# schematic.net
KiCad netlist of a schematic drawn in Altium Designer
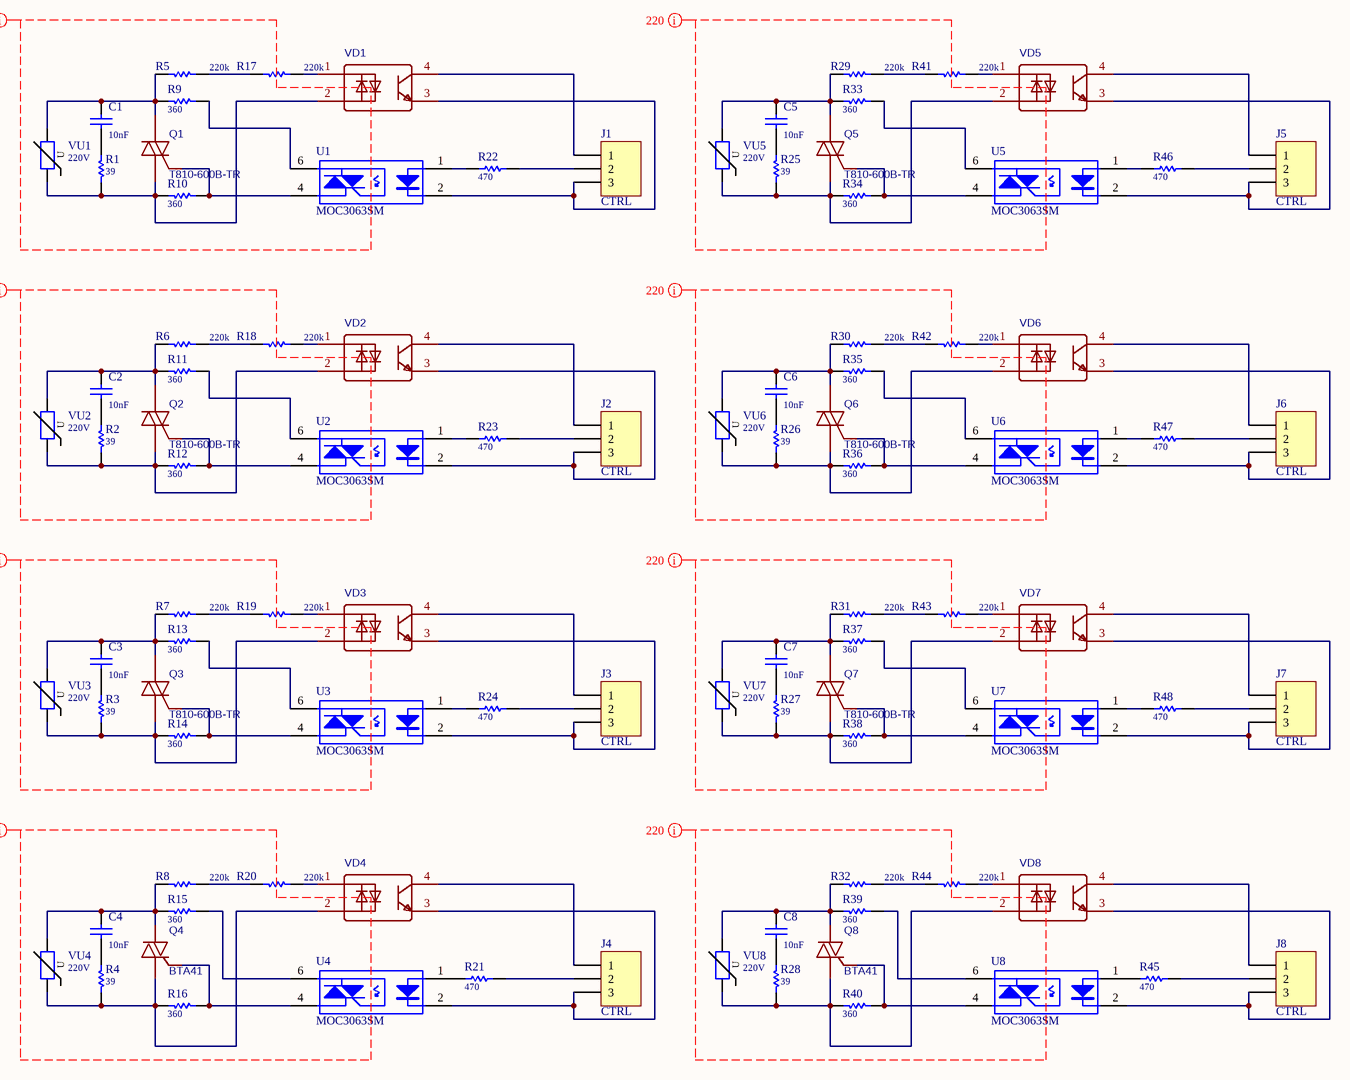
[diagram p0: schematic.SchDoc]

(export (version "E")
  (design (tool "Eeschema 10.0.6"))
  (components
    (comp (ref "C1")
      (value "10nF")
      (footprint "C1206")
      (description "10nF 1kV 1206")
      (libsource (lib "Miscellaneous Devices") (part "CAP"))
    )
    (comp (ref "C2")
      (value "10nF")
      (footprint "C1206")
      (description "10nF 1kV 1206")
      (libsource (lib "Miscellaneous Devices") (part "CAP"))
    )
    (comp (ref "C3")
      (value "10nF")
      (footprint "C1206")
      (description "10nF 1kV 1206")
      (libsource (lib "Miscellaneous Devices") (part "CAP"))
    )
    (comp (ref "C4")
      (value "10nF")
      (footprint "C1206")
      (description "10nF 1kV 1206")
      (libsource (lib "Miscellaneous Devices") (part "CAP"))
    )
    (comp (ref "C5")
      (value "10nF")
      (footprint "C1206")
      (description "10nF 1kV 1206")
      (libsource (lib "Miscellaneous Devices") (part "CAP"))
    )
    (comp (ref "C6")
      (value "10nF")
      (footprint "C1206")
      (description "10nF 1kV 1206")
      (libsource (lib "Miscellaneous Devices") (part "CAP"))
    )
    (comp (ref "C7")
      (value "10nF")
      (footprint "C1206")
      (description "10nF 1kV 1206")
      (libsource (lib "Miscellaneous Devices") (part "CAP"))
    )
    (comp (ref "C8")
      (value "10nF")
      (footprint "C1206")
      (description "10nF 1kV 1206")
      (libsource (lib "Miscellaneous Devices") (part "CAP"))
    )
    (comp (ref "J1")
      (value "CTRL")
      (footprint "CONN_MOLEX_532610371")
      (description "532610371")
      (libsource (lib "Miscellaneous Devices") (part "Header 3"))
    )
    (comp (ref "J2")
      (value "CTRL")
      (footprint "CONN_MOLEX_532610371")
      (description "532610371")
      (libsource (lib "Miscellaneous Devices") (part "Header 3"))
    )
    (comp (ref "J3")
      (value "CTRL")
      (footprint "CONN_MOLEX_532610371")
      (description "532610371")
      (libsource (lib "Miscellaneous Devices") (part "Header 3"))
    )
    (comp (ref "J4")
      (value "CTRL")
      (footprint "CONN_MOLEX_532610371")
      (description "532610371")
      (libsource (lib "Miscellaneous Devices") (part "Header 3"))
    )
    (comp (ref "J5")
      (value "CTRL")
      (footprint "CONN_MOLEX_532610371")
      (description "532610371")
      (libsource (lib "Miscellaneous Devices") (part "Header 3"))
    )
    (comp (ref "J6")
      (value "CTRL")
      (footprint "CONN_MOLEX_532610371")
      (description "532610371")
      (libsource (lib "Miscellaneous Devices") (part "Header 3"))
    )
    (comp (ref "J7")
      (value "CTRL")
      (footprint "CONN_MOLEX_532610371")
      (description "532610371")
      (libsource (lib "Miscellaneous Devices") (part "Header 3"))
    )
    (comp (ref "J8")
      (value "CTRL")
      (footprint "CONN_MOLEX_532610371")
      (description "532610371")
      (libsource (lib "Miscellaneous Devices") (part "Header 3"))
    )
    (comp (ref "Q1")
      (value "T810-600B-TR")
      (footprint "TO-252AA (DPAK)")
      (libsource (lib "altium-import") (part "root_3_mirrored_BTA16F_"))
    )
    (comp (ref "Q2")
      (value "T810-600B-TR")
      (footprint "TO-252AA (DPAK)")
      (libsource (lib "altium-import") (part "root_3_mirrored_BTA16F_"))
    )
    (comp (ref "Q3")
      (value "T810-600B-TR")
      (footprint "TO-252AA (DPAK)")
      (libsource (lib "altium-import") (part "root_3_mirrored_BTA16F_"))
    )
    (comp (ref "Q4")
      (value "BTA41")
      (footprint "TO-3P_L15.5-W4.6-P5.65-T")
      (libsource (lib "altium-import") (part "root_3_mirrored_BTA41_"))
    )
    (comp (ref "Q5")
      (value "T810-600B-TR")
      (footprint "TO-252AA (DPAK)")
      (libsource (lib "altium-import") (part "root_3_mirrored_BTA16F_"))
    )
    (comp (ref "Q6")
      (value "T810-600B-TR")
      (footprint "TO-252AA (DPAK)")
      (libsource (lib "altium-import") (part "root_3_mirrored_BTA16F_"))
    )
    (comp (ref "Q7")
      (value "T810-600B-TR")
      (footprint "TO-252AA (DPAK)")
      (libsource (lib "altium-import") (part "root_3_mirrored_BTA16F_"))
    )
    (comp (ref "Q8")
      (value "BTA41")
      (footprint "TO-3P_L15.5-W4.6-P5.65-T")
      (libsource (lib "altium-import") (part "root_3_mirrored_BTA41_"))
    )
    (comp (ref "R1")
      (value "39")
      (footprint "R1206")
      (description "39R 1206")
      (libsource (lib "Miscellaneous Devices") (part "RES"))
    )
    (comp (ref "R2")
      (value "39")
      (footprint "R1206")
      (description "39R 1206")
      (libsource (lib "Miscellaneous Devices") (part "RES"))
    )
    (comp (ref "R3")
      (value "39")
      (footprint "R1206")
      (description "39R 1206")
      (libsource (lib "Miscellaneous Devices") (part "RES"))
    )
    (comp (ref "R4")
      (value "39")
      (footprint "R1206")
      (description "39R 1206")
      (libsource (lib "Miscellaneous Devices") (part "RES"))
    )
    (comp (ref "R5")
      (value "220k")
      (footprint "R1206")
      (description "220k 1206")
      (libsource (lib "Miscellaneous Devices") (part "RES"))
    )
    (comp (ref "R6")
      (value "220k")
      (footprint "R1206")
      (description "220k 1206")
      (libsource (lib "Miscellaneous Devices") (part "RES"))
    )
    (comp (ref "R7")
      (value "220k")
      (footprint "R1206")
      (description "220k 1206")
      (libsource (lib "Miscellaneous Devices") (part "RES"))
    )
    (comp (ref "R8")
      (value "220k")
      (footprint "R1206")
      (description "220k 1206")
      (libsource (lib "Miscellaneous Devices") (part "RES"))
    )
    (comp (ref "R9")
      (value "360")
      (footprint "R2512")
      (description "360R 2512")
      (libsource (lib "Miscellaneous Devices") (part "RES"))
    )
    (comp (ref "R10")
      (value "360")
      (footprint "R2512")
      (description "360R 2512")
      (libsource (lib "Miscellaneous Devices") (part "RES"))
    )
    (comp (ref "R11")
      (value "360")
      (footprint "R2512")
      (description "360R 2512")
      (libsource (lib "Miscellaneous Devices") (part "RES"))
    )
    (comp (ref "R12")
      (value "360")
      (footprint "R2512")
      (description "360R 2512")
      (libsource (lib "Miscellaneous Devices") (part "RES"))
    )
    (comp (ref "R13")
      (value "360")
      (footprint "R2512")
      (description "360R 2512")
      (libsource (lib "Miscellaneous Devices") (part "RES"))
    )
    (comp (ref "R14")
      (value "360")
      (footprint "R2512")
      (description "360R 2512")
      (libsource (lib "Miscellaneous Devices") (part "RES"))
    )
    (comp (ref "R15")
      (value "360")
      (footprint "R2512")
      (description "360R 2512")
      (libsource (lib "Miscellaneous Devices") (part "RES"))
    )
    (comp (ref "R16")
      (value "360")
      (footprint "R2512")
      (description "360R 2512")
      (libsource (lib "Miscellaneous Devices") (part "RES"))
    )
    (comp (ref "R17")
      (value "220k")
      (footprint "R1206")
      (description "220k 1206")
      (libsource (lib "Miscellaneous Devices") (part "RES"))
    )
    (comp (ref "R18")
      (value "220k")
      (footprint "R1206")
      (description "220k 1206")
      (libsource (lib "Miscellaneous Devices") (part "RES"))
    )
    (comp (ref "R19")
      (value "220k")
      (footprint "R1206")
      (description "220k 1206")
      (libsource (lib "Miscellaneous Devices") (part "RES"))
    )
    (comp (ref "R20")
      (value "220k")
      (footprint "R1206")
      (description "220k 1206")
      (libsource (lib "Miscellaneous Devices") (part "RES"))
    )
    (comp (ref "R21")
      (value "470")
      (footprint "R0603")
      (description "470R 0603")
      (libsource (lib "Miscellaneous Devices") (part "RES"))
    )
    (comp (ref "R22")
      (value "470")
      (footprint "R0603")
      (description "470R 0603")
      (libsource (lib "Miscellaneous Devices") (part "RES"))
    )
    (comp (ref "R23")
      (value "470")
      (footprint "R0603")
      (description "470R 0603")
      (libsource (lib "Miscellaneous Devices") (part "RES"))
    )
    (comp (ref "R24")
      (value "470")
      (footprint "R0603")
      (description "470R 0603")
      (libsource (lib "Miscellaneous Devices") (part "RES"))
    )
    (comp (ref "R25")
      (value "39")
      (footprint "R1206")
      (description "39R 1206")
      (libsource (lib "Miscellaneous Devices") (part "RES"))
    )
    (comp (ref "R26")
      (value "39")
      (footprint "R1206")
      (description "39R 1206")
      (libsource (lib "Miscellaneous Devices") (part "RES"))
    )
    (comp (ref "R27")
      (value "39")
      (footprint "R1206")
      (description "39R 1206")
      (libsource (lib "Miscellaneous Devices") (part "RES"))
    )
    (comp (ref "R28")
      (value "39")
      (footprint "R1206")
      (description "39R 1206")
      (libsource (lib "Miscellaneous Devices") (part "RES"))
    )
    (comp (ref "R29")
      (value "220k")
      (footprint "R1206")
      (description "220k 1206")
      (libsource (lib "Miscellaneous Devices") (part "RES"))
    )
    (comp (ref "R30")
      (value "220k")
      (footprint "R1206")
      (description "220k 1206")
      (libsource (lib "Miscellaneous Devices") (part "RES"))
    )
    (comp (ref "R31")
      (value "220k")
      (footprint "R1206")
      (description "220k 1206")
      (libsource (lib "Miscellaneous Devices") (part "RES"))
    )
    (comp (ref "R32")
      (value "220k")
      (footprint "R1206")
      (description "220k 1206")
      (libsource (lib "Miscellaneous Devices") (part "RES"))
    )
    (comp (ref "R33")
      (value "360")
      (footprint "R2512")
      (description "360R 2512")
      (libsource (lib "Miscellaneous Devices") (part "RES"))
    )
    (comp (ref "R34")
      (value "360")
      (footprint "R2512")
      (description "360R 2512")
      (libsource (lib "Miscellaneous Devices") (part "RES"))
    )
    (comp (ref "R35")
      (value "360")
      (footprint "R2512")
      (description "360R 2512")
      (libsource (lib "Miscellaneous Devices") (part "RES"))
    )
    (comp (ref "R36")
      (value "360")
      (footprint "R2512")
      (description "360R 2512")
      (libsource (lib "Miscellaneous Devices") (part "RES"))
    )
    (comp (ref "R37")
      (value "360")
      (footprint "R2512")
      (description "360R 2512")
      (libsource (lib "Miscellaneous Devices") (part "RES"))
    )
    (comp (ref "R38")
      (value "360")
      (footprint "R2512")
      (description "360R 2512")
      (libsource (lib "Miscellaneous Devices") (part "RES"))
    )
    (comp (ref "R39")
      (value "360")
      (footprint "R2512")
      (description "360R 2512")
      (libsource (lib "Miscellaneous Devices") (part "RES"))
    )
    (comp (ref "R40")
      (value "360")
      (footprint "R2512")
      (description "360R 2512")
      (libsource (lib "Miscellaneous Devices") (part "RES"))
    )
    (comp (ref "R41")
      (value "220k")
      (footprint "R1206")
      (description "220k 1206")
      (libsource (lib "Miscellaneous Devices") (part "RES"))
    )
    (comp (ref "R42")
      (value "220k")
      (footprint "R1206")
      (description "220k 1206")
      (libsource (lib "Miscellaneous Devices") (part "RES"))
    )
    (comp (ref "R43")
      (value "220k")
      (footprint "R1206")
      (description "220k 1206")
      (libsource (lib "Miscellaneous Devices") (part "RES"))
    )
    (comp (ref "R44")
      (value "220k")
      (footprint "R1206")
      (description "220k 1206")
      (libsource (lib "Miscellaneous Devices") (part "RES"))
    )
    (comp (ref "R45")
      (value "470")
      (footprint "R0603")
      (description "470R 0603")
      (libsource (lib "Miscellaneous Devices") (part "RES"))
    )
    (comp (ref "R46")
      (value "470")
      (footprint "R0603")
      (description "470R 0603")
      (libsource (lib "Miscellaneous Devices") (part "RES"))
    )
    (comp (ref "R47")
      (value "470")
      (footprint "R0603")
      (description "470R 0603")
      (libsource (lib "Miscellaneous Devices") (part "RES"))
    )
    (comp (ref "R48")
      (value "470")
      (footprint "R0603")
      (description "470R 0603")
      (libsource (lib "Miscellaneous Devices") (part "RES"))
    )
    (comp (ref "U1")
      (value "MOC3063SM")
      (footprint "SMD-6")
      (description "MOC3063S-TA1")
      (libsource (lib "Miscellaneous Devices") (part "MOC3063SM"))
    )
    (comp (ref "U2")
      (value "MOC3063SM")
      (footprint "SMD-6")
      (description "MOC3063S-TA1")
      (libsource (lib "Miscellaneous Devices") (part "MOC3063SM"))
    )
    (comp (ref "U3")
      (value "MOC3063SM")
      (footprint "SMD-6")
      (description "MOC3063S-TA1")
      (libsource (lib "Miscellaneous Devices") (part "MOC3063SM"))
    )
    (comp (ref "U4")
      (value "MOC3063SM")
      (footprint "SMD-6")
      (description "MOC3063S-TA1")
      (libsource (lib "Miscellaneous Devices") (part "MOC3063SM"))
    )
    (comp (ref "U5")
      (value "MOC3063SM")
      (footprint "SMD-6")
      (description "MOC3063S-TA1")
      (libsource (lib "Miscellaneous Devices") (part "MOC3063SM"))
    )
    (comp (ref "U6")
      (value "MOC3063SM")
      (footprint "SMD-6")
      (description "MOC3063S-TA1")
      (libsource (lib "Miscellaneous Devices") (part "MOC3063SM"))
    )
    (comp (ref "U7")
      (value "MOC3063SM")
      (footprint "SMD-6")
      (description "MOC3063S-TA1")
      (libsource (lib "Miscellaneous Devices") (part "MOC3063SM"))
    )
    (comp (ref "U8")
      (value "MOC3063SM")
      (footprint "SMD-6")
      (description "MOC3063S-TA1")
      (libsource (lib "Miscellaneous Devices") (part "MOC3063SM"))
    )
    (comp (ref "VD1")
      (value "EL3H4(A)(TA)-VG")
      (footprint "SOP-4_L4.4-W2.8-P1.27-LS7.0-TL")
      (libsource (lib "altium-import") (part "root_0_EL3H4(A)(TA)-VG_"))
    )
    (comp (ref "VD2")
      (value "EL3H4(A)(TA)-VG")
      (footprint "SOP-4_L4.4-W2.8-P1.27-LS7.0-TL")
      (libsource (lib "altium-import") (part "root_0_EL3H4(A)(TA)-VG_"))
    )
    (comp (ref "VD3")
      (value "EL3H4(A)(TA)-VG")
      (footprint "SOP-4_L4.4-W2.8-P1.27-LS7.0-TL")
      (libsource (lib "altium-import") (part "root_0_EL3H4(A)(TA)-VG_"))
    )
    (comp (ref "VD4")
      (value "EL3H4(A)(TA)-VG")
      (footprint "SOP-4_L4.4-W2.8-P1.27-LS7.0-TL")
      (libsource (lib "altium-import") (part "root_0_EL3H4(A)(TA)-VG_"))
    )
    (comp (ref "VD5")
      (value "EL3H4(A)(TA)-VG")
      (footprint "SOP-4_L4.4-W2.8-P1.27-LS7.0-TL")
      (libsource (lib "altium-import") (part "root_0_EL3H4(A)(TA)-VG_"))
    )
    (comp (ref "VD6")
      (value "EL3H4(A)(TA)-VG")
      (footprint "SOP-4_L4.4-W2.8-P1.27-LS7.0-TL")
      (libsource (lib "altium-import") (part "root_0_EL3H4(A)(TA)-VG_"))
    )
    (comp (ref "VD7")
      (value "EL3H4(A)(TA)-VG")
      (footprint "SOP-4_L4.4-W2.8-P1.27-LS7.0-TL")
      (libsource (lib "altium-import") (part "root_0_EL3H4(A)(TA)-VG_"))
    )
    (comp (ref "VD8")
      (value "EL3H4(A)(TA)-VG")
      (footprint "SOP-4_L4.4-W2.8-P1.27-LS7.0-TL")
      (libsource (lib "altium-import") (part "root_0_EL3H4(A)(TA)-VG_"))
    )
    (comp (ref "VU1")
      (value "220V")
      (footprint "SMC")
      (description "3225D471KJ")
      (libsource (lib "Schlib1") (part "RES"))
    )
    (comp (ref "VU2")
      (value "220V")
      (footprint "SMC")
      (description "3225D471KJ")
      (libsource (lib "Schlib1") (part "RES"))
    )
    (comp (ref "VU3")
      (value "220V")
      (footprint "SMC")
      (description "3225D471KJ")
      (libsource (lib "Schlib1") (part "RES"))
    )
    (comp (ref "VU4")
      (value "220V")
      (footprint "SMC")
      (description "3225D471KJ")
      (libsource (lib "Schlib1") (part "RES"))
    )
    (comp (ref "VU5")
      (value "220V")
      (footprint "SMC")
      (description "3225D471KJ")
      (libsource (lib "Schlib1") (part "RES"))
    )
    (comp (ref "VU6")
      (value "220V")
      (footprint "SMC")
      (description "3225D471KJ")
      (libsource (lib "Schlib1") (part "RES"))
    )
    (comp (ref "VU7")
      (value "220V")
      (footprint "SMC")
      (description "3225D471KJ")
      (libsource (lib "Schlib1") (part "RES"))
    )
    (comp (ref "VU8")
      (value "220V")
      (footprint "SMC")
      (description "3225D471KJ")
      (libsource (lib "Schlib1") (part "RES"))
    )
  )
  (nets
    (net (code "1") (name "Net-(C1-Pad1)") (class "Default")
      (node (ref "C1") (pin "1") (pinfunction "1_1") (pintype "passive"))
      (node (ref "R1") (pin "2") (pinfunction "2_2") (pintype "passive"))
    )
    (net (code "2") (name "Net-(C2-Pad1)") (class "Default")
      (node (ref "C2") (pin "1") (pinfunction "1_1") (pintype "passive"))
      (node (ref "R2") (pin "2") (pinfunction "2_2") (pintype "passive"))
    )
    (net (code "3") (name "Net-(C3-Pad1)") (class "Default")
      (node (ref "C3") (pin "1") (pinfunction "1_1") (pintype "passive"))
      (node (ref "R3") (pin "2") (pinfunction "2_2") (pintype "passive"))
    )
    (net (code "4") (name "Net-(C4-Pad1)") (class "Default")
      (node (ref "C4") (pin "1") (pinfunction "1_1") (pintype "passive"))
      (node (ref "R4") (pin "2") (pinfunction "2_2") (pintype "passive"))
    )
    (net (code "5") (name "Net-(C5-Pad1)") (class "Default")
      (node (ref "C5") (pin "1") (pinfunction "1_1") (pintype "passive"))
      (node (ref "R25") (pin "2") (pinfunction "2_2") (pintype "passive"))
    )
    (net (code "6") (name "Net-(C6-Pad1)") (class "Default")
      (node (ref "C6") (pin "1") (pinfunction "1_1") (pintype "passive"))
      (node (ref "R26") (pin "2") (pinfunction "2_2") (pintype "passive"))
    )
    (net (code "7") (name "Net-(C7-Pad1)") (class "Default")
      (node (ref "C7") (pin "1") (pinfunction "1_1") (pintype "passive"))
      (node (ref "R27") (pin "2") (pinfunction "2_2") (pintype "passive"))
    )
    (net (code "8") (name "Net-(C8-Pad1)") (class "Default")
      (node (ref "C8") (pin "1") (pinfunction "1_1") (pintype "passive"))
      (node (ref "R28") (pin "2") (pinfunction "2_2") (pintype "passive"))
    )
    (net (code "9") (name "Net-(J1-Pad2)") (class "Default")
      (node (ref "J1") (pin "2") (pinfunction "2_2") (pintype "passive"))
      (node (ref "R22") (pin "2") (pinfunction "2_2") (pintype "passive"))
    )
    (net (code "10") (name "Net-(J2-Pad2)") (class "Default")
      (node (ref "J2") (pin "2") (pinfunction "2_2") (pintype "passive"))
      (node (ref "R23") (pin "2") (pinfunction "2_2") (pintype "passive"))
    )
    (net (code "11") (name "Net-(J3-Pad2)") (class "Default")
      (node (ref "J3") (pin "2") (pinfunction "2_2") (pintype "passive"))
      (node (ref "R24") (pin "2") (pinfunction "2_2") (pintype "passive"))
    )
    (net (code "12") (name "Net-(J4-Pad2)") (class "Default")
      (node (ref "J4") (pin "2") (pinfunction "2_2") (pintype "passive"))
      (node (ref "R21") (pin "2") (pinfunction "2_2") (pintype "passive"))
    )
    (net (code "13") (name "Net-(J5-Pad2)") (class "Default")
      (node (ref "J5") (pin "2") (pinfunction "2_2") (pintype "passive"))
      (node (ref "R46") (pin "2") (pinfunction "2_2") (pintype "passive"))
    )
    (net (code "14") (name "Net-(J6-Pad2)") (class "Default")
      (node (ref "J6") (pin "2") (pinfunction "2_2") (pintype "passive"))
      (node (ref "R47") (pin "2") (pinfunction "2_2") (pintype "passive"))
    )
    (net (code "15") (name "Net-(J7-Pad2)") (class "Default")
      (node (ref "J7") (pin "2") (pinfunction "2_2") (pintype "passive"))
      (node (ref "R48") (pin "2") (pinfunction "2_2") (pintype "passive"))
    )
    (net (code "16") (name "Net-(J8-Pad2)") (class "Default")
      (node (ref "J8") (pin "2") (pinfunction "2_2") (pintype "passive"))
      (node (ref "R45") (pin "2") (pinfunction "2_2") (pintype "passive"))
    )
    (net (code "17") (name "Net-(Q1-G)") (class "Default")
      (node (ref "Q1") (pin "3") (pinfunction "G_3") (pintype "passive"))
      (node (ref "R10") (pin "2") (pinfunction "2_2") (pintype "passive"))
      (node (ref "U1") (pin "4") (pinfunction "MAIN_TERM_4") (pintype "passive"))
    )
    (net (code "18") (name "Net-(Q1-T1)") (class "Default")
      (node (ref "Q1") (pin "1") (pinfunction "T1_1") (pintype "passive"))
      (node (ref "R1") (pin "1") (pinfunction "1_1") (pintype "passive"))
      (node (ref "R10") (pin "1") (pinfunction "1_1") (pintype "passive"))
      (node (ref "VD1") (pin "2") (pinfunction "Cathode_/_Anode_2") (pintype "passive"))
      (node (ref "VU1") (pin "1") (pinfunction "1_1") (pintype "passive"))
    )
    (net (code "19") (name "Net-(Q1-T2)") (class "Default")
      (node (ref "C1") (pin "2") (pinfunction "2_2") (pintype "passive"))
      (node (ref "Q1") (pin "2") (pinfunction "T2_2") (pintype "passive"))
      (node (ref "R5") (pin "1") (pinfunction "1_1") (pintype "passive"))
      (node (ref "R9") (pin "2") (pinfunction "2_2") (pintype "passive"))
      (node (ref "VU1") (pin "2") (pinfunction "2_2") (pintype "passive"))
    )
    (net (code "20") (name "Net-(Q2-G)") (class "Default")
      (node (ref "Q2") (pin "3") (pinfunction "G_3") (pintype "passive"))
      (node (ref "R12") (pin "2") (pinfunction "2_2") (pintype "passive"))
      (node (ref "U2") (pin "4") (pinfunction "MAIN_TERM_4") (pintype "passive"))
    )
    (net (code "21") (name "Net-(Q2-T1)") (class "Default")
      (node (ref "Q2") (pin "1") (pinfunction "T1_1") (pintype "passive"))
      (node (ref "R12") (pin "1") (pinfunction "1_1") (pintype "passive"))
      (node (ref "R2") (pin "1") (pinfunction "1_1") (pintype "passive"))
      (node (ref "VD2") (pin "2") (pinfunction "Cathode_/_Anode_2") (pintype "passive"))
      (node (ref "VU2") (pin "1") (pinfunction "1_1") (pintype "passive"))
    )
    (net (code "22") (name "Net-(Q2-T2)") (class "Default")
      (node (ref "C2") (pin "2") (pinfunction "2_2") (pintype "passive"))
      (node (ref "Q2") (pin "2") (pinfunction "T2_2") (pintype "passive"))
      (node (ref "R11") (pin "2") (pinfunction "2_2") (pintype "passive"))
      (node (ref "R6") (pin "1") (pinfunction "1_1") (pintype "passive"))
      (node (ref "VU2") (pin "2") (pinfunction "2_2") (pintype "passive"))
    )
    (net (code "23") (name "Net-(Q3-G)") (class "Default")
      (node (ref "Q3") (pin "3") (pinfunction "G_3") (pintype "passive"))
      (node (ref "R14") (pin "2") (pinfunction "2_2") (pintype "passive"))
      (node (ref "U3") (pin "4") (pinfunction "MAIN_TERM_4") (pintype "passive"))
    )
    (net (code "24") (name "Net-(Q3-T1)") (class "Default")
      (node (ref "Q3") (pin "1") (pinfunction "T1_1") (pintype "passive"))
      (node (ref "R14") (pin "1") (pinfunction "1_1") (pintype "passive"))
      (node (ref "R3") (pin "1") (pinfunction "1_1") (pintype "passive"))
      (node (ref "VD3") (pin "2") (pinfunction "Cathode_/_Anode_2") (pintype "passive"))
      (node (ref "VU3") (pin "1") (pinfunction "1_1") (pintype "passive"))
    )
    (net (code "25") (name "Net-(Q3-T2)") (class "Default")
      (node (ref "C3") (pin "2") (pinfunction "2_2") (pintype "passive"))
      (node (ref "Q3") (pin "2") (pinfunction "T2_2") (pintype "passive"))
      (node (ref "R13") (pin "2") (pinfunction "2_2") (pintype "passive"))
      (node (ref "R7") (pin "1") (pinfunction "1_1") (pintype "passive"))
      (node (ref "VU3") (pin "2") (pinfunction "2_2") (pintype "passive"))
    )
    (net (code "26") (name "Net-(Q4-G)") (class "Default")
      (node (ref "Q4") (pin "3") (pinfunction "G_3") (pintype "passive"))
      (node (ref "R16") (pin "2") (pinfunction "2_2") (pintype "passive"))
      (node (ref "U4") (pin "4") (pinfunction "MAIN_TERM_4") (pintype "passive"))
    )
    (net (code "27") (name "Net-(Q4-T1)") (class "Default")
      (node (ref "Q4") (pin "1") (pinfunction "T1_1") (pintype "passive"))
      (node (ref "R16") (pin "1") (pinfunction "1_1") (pintype "passive"))
      (node (ref "R4") (pin "1") (pinfunction "1_1") (pintype "passive"))
      (node (ref "VD4") (pin "2") (pinfunction "Cathode_/_Anode_2") (pintype "passive"))
      (node (ref "VU4") (pin "1") (pinfunction "1_1") (pintype "passive"))
    )
    (net (code "28") (name "Net-(Q4-T2)") (class "Default")
      (node (ref "C4") (pin "2") (pinfunction "2_2") (pintype "passive"))
      (node (ref "Q4") (pin "2") (pinfunction "T2_2") (pintype "passive"))
      (node (ref "R15") (pin "2") (pinfunction "2_2") (pintype "passive"))
      (node (ref "R8") (pin "1") (pinfunction "1_1") (pintype "passive"))
      (node (ref "VU4") (pin "2") (pinfunction "2_2") (pintype "passive"))
    )
    (net (code "29") (name "Net-(Q5-G)") (class "Default")
      (node (ref "Q5") (pin "3") (pinfunction "G_3") (pintype "passive"))
      (node (ref "R34") (pin "2") (pinfunction "2_2") (pintype "passive"))
      (node (ref "U5") (pin "4") (pinfunction "MAIN_TERM_4") (pintype "passive"))
    )
    (net (code "30") (name "Net-(Q5-T1)") (class "Default")
      (node (ref "Q5") (pin "1") (pinfunction "T1_1") (pintype "passive"))
      (node (ref "R25") (pin "1") (pinfunction "1_1") (pintype "passive"))
      (node (ref "R34") (pin "1") (pinfunction "1_1") (pintype "passive"))
      (node (ref "VD5") (pin "2") (pinfunction "Cathode_/_Anode_2") (pintype "passive"))
      (node (ref "VU5") (pin "1") (pinfunction "1_1") (pintype "passive"))
    )
    (net (code "31") (name "Net-(Q5-T2)") (class "Default")
      (node (ref "C5") (pin "2") (pinfunction "2_2") (pintype "passive"))
      (node (ref "Q5") (pin "2") (pinfunction "T2_2") (pintype "passive"))
      (node (ref "R29") (pin "1") (pinfunction "1_1") (pintype "passive"))
      (node (ref "R33") (pin "2") (pinfunction "2_2") (pintype "passive"))
      (node (ref "VU5") (pin "2") (pinfunction "2_2") (pintype "passive"))
    )
    (net (code "32") (name "Net-(Q6-G)") (class "Default")
      (node (ref "Q6") (pin "3") (pinfunction "G_3") (pintype "passive"))
      (node (ref "R36") (pin "2") (pinfunction "2_2") (pintype "passive"))
      (node (ref "U6") (pin "4") (pinfunction "MAIN_TERM_4") (pintype "passive"))
    )
    (net (code "33") (name "Net-(Q6-T1)") (class "Default")
      (node (ref "Q6") (pin "1") (pinfunction "T1_1") (pintype "passive"))
      (node (ref "R26") (pin "1") (pinfunction "1_1") (pintype "passive"))
      (node (ref "R36") (pin "1") (pinfunction "1_1") (pintype "passive"))
      (node (ref "VD6") (pin "2") (pinfunction "Cathode_/_Anode_2") (pintype "passive"))
      (node (ref "VU6") (pin "1") (pinfunction "1_1") (pintype "passive"))
    )
    (net (code "34") (name "Net-(Q6-T2)") (class "Default")
      (node (ref "C6") (pin "2") (pinfunction "2_2") (pintype "passive"))
      (node (ref "Q6") (pin "2") (pinfunction "T2_2") (pintype "passive"))
      (node (ref "R30") (pin "1") (pinfunction "1_1") (pintype "passive"))
      (node (ref "R35") (pin "2") (pinfunction "2_2") (pintype "passive"))
      (node (ref "VU6") (pin "2") (pinfunction "2_2") (pintype "passive"))
    )
    (net (code "35") (name "Net-(Q7-G)") (class "Default")
      (node (ref "Q7") (pin "3") (pinfunction "G_3") (pintype "passive"))
      (node (ref "R38") (pin "2") (pinfunction "2_2") (pintype "passive"))
      (node (ref "U7") (pin "4") (pinfunction "MAIN_TERM_4") (pintype "passive"))
    )
    (net (code "36") (name "Net-(Q7-T1)") (class "Default")
      (node (ref "Q7") (pin "1") (pinfunction "T1_1") (pintype "passive"))
      (node (ref "R27") (pin "1") (pinfunction "1_1") (pintype "passive"))
      (node (ref "R38") (pin "1") (pinfunction "1_1") (pintype "passive"))
      (node (ref "VD7") (pin "2") (pinfunction "Cathode_/_Anode_2") (pintype "passive"))
      (node (ref "VU7") (pin "1") (pinfunction "1_1") (pintype "passive"))
    )
    (net (code "37") (name "Net-(Q7-T2)") (class "Default")
      (node (ref "C7") (pin "2") (pinfunction "2_2") (pintype "passive"))
      (node (ref "Q7") (pin "2") (pinfunction "T2_2") (pintype "passive"))
      (node (ref "R31") (pin "1") (pinfunction "1_1") (pintype "passive"))
      (node (ref "R37") (pin "2") (pinfunction "2_2") (pintype "passive"))
      (node (ref "VU7") (pin "2") (pinfunction "2_2") (pintype "passive"))
    )
    (net (code "38") (name "Net-(Q8-G)") (class "Default")
      (node (ref "Q8") (pin "3") (pinfunction "G_3") (pintype "passive"))
      (node (ref "R40") (pin "2") (pinfunction "2_2") (pintype "passive"))
      (node (ref "U8") (pin "4") (pinfunction "MAIN_TERM_4") (pintype "passive"))
    )
    (net (code "39") (name "Net-(Q8-T1)") (class "Default")
      (node (ref "Q8") (pin "1") (pinfunction "T1_1") (pintype "passive"))
      (node (ref "R28") (pin "1") (pinfunction "1_1") (pintype "passive"))
      (node (ref "R40") (pin "1") (pinfunction "1_1") (pintype "passive"))
      (node (ref "VD8") (pin "2") (pinfunction "Cathode_/_Anode_2") (pintype "passive"))
      (node (ref "VU8") (pin "1") (pinfunction "1_1") (pintype "passive"))
    )
    (net (code "40") (name "Net-(Q8-T2)") (class "Default")
      (node (ref "C8") (pin "2") (pinfunction "2_2") (pintype "passive"))
      (node (ref "Q8") (pin "2") (pinfunction "T2_2") (pintype "passive"))
      (node (ref "R32") (pin "1") (pinfunction "1_1") (pintype "passive"))
      (node (ref "R39") (pin "2") (pinfunction "2_2") (pintype "passive"))
      (node (ref "VU8") (pin "2") (pinfunction "2_2") (pintype "passive"))
    )
    (net (code "41") (name "Net-(R9-Pad1)") (class "Default")
      (node (ref "R9") (pin "1") (pinfunction "1_1") (pintype "passive"))
      (node (ref "U1") (pin "6") (pinfunction "MAIN_TERM_6") (pintype "passive"))
    )
    (net (code "42") (name "Net-(R11-Pad1)") (class "Default")
      (node (ref "R11") (pin "1") (pinfunction "1_1") (pintype "passive"))
      (node (ref "U2") (pin "6") (pinfunction "MAIN_TERM_6") (pintype "passive"))
    )
    (net (code "43") (name "Net-(R13-Pad1)") (class "Default")
      (node (ref "R13") (pin "1") (pinfunction "1_1") (pintype "passive"))
      (node (ref "U3") (pin "6") (pinfunction "MAIN_TERM_6") (pintype "passive"))
    )
    (net (code "44") (name "Net-(R15-Pad1)") (class "Default")
      (node (ref "R15") (pin "1") (pinfunction "1_1") (pintype "passive"))
      (node (ref "U4") (pin "6") (pinfunction "MAIN_TERM_6") (pintype "passive"))
    )
    (net (code "45") (name "Net-(R17-Pad1)") (class "Default")
      (node (ref "R17") (pin "1") (pinfunction "1_1") (pintype "passive"))
      (node (ref "R5") (pin "2") (pinfunction "2_2") (pintype "passive"))
    )
    (net (code "46") (name "Net-(R18-Pad1)") (class "Default")
      (node (ref "R18") (pin "1") (pinfunction "1_1") (pintype "passive"))
      (node (ref "R6") (pin "2") (pinfunction "2_2") (pintype "passive"))
    )
    (net (code "47") (name "Net-(R19-Pad1)") (class "Default")
      (node (ref "R19") (pin "1") (pinfunction "1_1") (pintype "passive"))
      (node (ref "R7") (pin "2") (pinfunction "2_2") (pintype "passive"))
    )
    (net (code "48") (name "Net-(R20-Pad1)") (class "Default")
      (node (ref "R20") (pin "1") (pinfunction "1_1") (pintype "passive"))
      (node (ref "R8") (pin "2") (pinfunction "2_2") (pintype "passive"))
    )
    (net (code "49") (name "Net-(R29-Pad2)") (class "Default")
      (node (ref "R29") (pin "2") (pinfunction "2_2") (pintype "passive"))
      (node (ref "R41") (pin "1") (pinfunction "1_1") (pintype "passive"))
    )
    (net (code "50") (name "Net-(R30-Pad2)") (class "Default")
      (node (ref "R30") (pin "2") (pinfunction "2_2") (pintype "passive"))
      (node (ref "R42") (pin "1") (pinfunction "1_1") (pintype "passive"))
    )
    (net (code "51") (name "Net-(R31-Pad2)") (class "Default")
      (node (ref "R31") (pin "2") (pinfunction "2_2") (pintype "passive"))
      (node (ref "R43") (pin "1") (pinfunction "1_1") (pintype "passive"))
    )
    (net (code "52") (name "Net-(R32-Pad2)") (class "Default")
      (node (ref "R32") (pin "2") (pinfunction "2_2") (pintype "passive"))
      (node (ref "R44") (pin "1") (pinfunction "1_1") (pintype "passive"))
    )
    (net (code "53") (name "Net-(R33-Pad1)") (class "Default")
      (node (ref "R33") (pin "1") (pinfunction "1_1") (pintype "passive"))
      (node (ref "U5") (pin "6") (pinfunction "MAIN_TERM_6") (pintype "passive"))
    )
    (net (code "54") (name "Net-(R35-Pad1)") (class "Default")
      (node (ref "R35") (pin "1") (pinfunction "1_1") (pintype "passive"))
      (node (ref "U6") (pin "6") (pinfunction "MAIN_TERM_6") (pintype "passive"))
    )
    (net (code "55") (name "Net-(R37-Pad1)") (class "Default")
      (node (ref "R37") (pin "1") (pinfunction "1_1") (pintype "passive"))
      (node (ref "U7") (pin "6") (pinfunction "MAIN_TERM_6") (pintype "passive"))
    )
    (net (code "56") (name "Net-(R39-Pad1)") (class "Default")
      (node (ref "R39") (pin "1") (pinfunction "1_1") (pintype "passive"))
      (node (ref "U8") (pin "6") (pinfunction "MAIN_TERM_6") (pintype "passive"))
    )
    (net (code "57") (name "Net-(U1-ANODE)") (class "Default")
      (node (ref "R22") (pin "1") (pinfunction "1_1") (pintype "passive"))
      (node (ref "U1") (pin "1") (pinfunction "ANODE_1") (pintype "passive"))
    )
    (net (code "58") (name "Net-(U1-CATHODE)") (class "Default")
      (node (ref "J1") (pin "3") (pinfunction "3_3") (pintype "passive"))
      (node (ref "U1") (pin "2") (pinfunction "CATHODE_2") (pintype "passive"))
      (node (ref "VD1") (pin "3") (pinfunction "Emitter_3") (pintype "passive"))
    )
    (net (code "59") (name "Net-(U2-ANODE)") (class "Default")
      (node (ref "R23") (pin "1") (pinfunction "1_1") (pintype "passive"))
      (node (ref "U2") (pin "1") (pinfunction "ANODE_1") (pintype "passive"))
    )
    (net (code "60") (name "Net-(U2-CATHODE)") (class "Default")
      (node (ref "J2") (pin "3") (pinfunction "3_3") (pintype "passive"))
      (node (ref "U2") (pin "2") (pinfunction "CATHODE_2") (pintype "passive"))
      (node (ref "VD2") (pin "3") (pinfunction "Emitter_3") (pintype "passive"))
    )
    (net (code "61") (name "Net-(U3-ANODE)") (class "Default")
      (node (ref "R24") (pin "1") (pinfunction "1_1") (pintype "passive"))
      (node (ref "U3") (pin "1") (pinfunction "ANODE_1") (pintype "passive"))
    )
    (net (code "62") (name "Net-(U3-CATHODE)") (class "Default")
      (node (ref "J3") (pin "3") (pinfunction "3_3") (pintype "passive"))
      (node (ref "U3") (pin "2") (pinfunction "CATHODE_2") (pintype "passive"))
      (node (ref "VD3") (pin "3") (pinfunction "Emitter_3") (pintype "passive"))
    )
    (net (code "63") (name "Net-(U4-ANODE)") (class "Default")
      (node (ref "R21") (pin "1") (pinfunction "1_1") (pintype "passive"))
      (node (ref "U4") (pin "1") (pinfunction "ANODE_1") (pintype "passive"))
    )
    (net (code "64") (name "Net-(U4-CATHODE)") (class "Default")
      (node (ref "J4") (pin "3") (pinfunction "3_3") (pintype "passive"))
      (node (ref "U4") (pin "2") (pinfunction "CATHODE_2") (pintype "passive"))
      (node (ref "VD4") (pin "3") (pinfunction "Emitter_3") (pintype "passive"))
    )
    (net (code "65") (name "Net-(U5-ANODE)") (class "Default")
      (node (ref "R46") (pin "1") (pinfunction "1_1") (pintype "passive"))
      (node (ref "U5") (pin "1") (pinfunction "ANODE_1") (pintype "passive"))
    )
    (net (code "66") (name "Net-(U5-CATHODE)") (class "Default")
      (node (ref "J5") (pin "3") (pinfunction "3_3") (pintype "passive"))
      (node (ref "U5") (pin "2") (pinfunction "CATHODE_2") (pintype "passive"))
      (node (ref "VD5") (pin "3") (pinfunction "Emitter_3") (pintype "passive"))
    )
    (net (code "67") (name "Net-(U6-ANODE)") (class "Default")
      (node (ref "R47") (pin "1") (pinfunction "1_1") (pintype "passive"))
      (node (ref "U6") (pin "1") (pinfunction "ANODE_1") (pintype "passive"))
    )
    (net (code "68") (name "Net-(U6-CATHODE)") (class "Default")
      (node (ref "J6") (pin "3") (pinfunction "3_3") (pintype "passive"))
      (node (ref "U6") (pin "2") (pinfunction "CATHODE_2") (pintype "passive"))
      (node (ref "VD6") (pin "3") (pinfunction "Emitter_3") (pintype "passive"))
    )
    (net (code "69") (name "Net-(U7-ANODE)") (class "Default")
      (node (ref "R48") (pin "1") (pinfunction "1_1") (pintype "passive"))
      (node (ref "U7") (pin "1") (pinfunction "ANODE_1") (pintype "passive"))
    )
    (net (code "70") (name "Net-(U7-CATHODE)") (class "Default")
      (node (ref "J7") (pin "3") (pinfunction "3_3") (pintype "passive"))
      (node (ref "U7") (pin "2") (pinfunction "CATHODE_2") (pintype "passive"))
      (node (ref "VD7") (pin "3") (pinfunction "Emitter_3") (pintype "passive"))
    )
    (net (code "71") (name "Net-(U8-ANODE)") (class "Default")
      (node (ref "R45") (pin "1") (pinfunction "1_1") (pintype "passive"))
      (node (ref "U8") (pin "1") (pinfunction "ANODE_1") (pintype "passive"))
    )
    (net (code "72") (name "Net-(U8-CATHODE)") (class "Default")
      (node (ref "J8") (pin "3") (pinfunction "3_3") (pintype "passive"))
      (node (ref "U8") (pin "2") (pinfunction "CATHODE_2") (pintype "passive"))
      (node (ref "VD8") (pin "3") (pinfunction "Emitter_3") (pintype "passive"))
    )
    (net (code "73") (name "Net-(VD1-Anode_{slash}_Cathode)") (class "Default")
      (node (ref "R17") (pin "2") (pinfunction "2_2") (pintype "passive"))
      (node (ref "VD1") (pin "1") (pinfunction "Anode_/_Cathode_1") (pintype "passive"))
    )
    (net (code "74") (name "Net-(VD1-Collector)") (class "Default")
      (node (ref "J1") (pin "1") (pinfunction "1_1") (pintype "passive"))
      (node (ref "VD1") (pin "4") (pinfunction "Collector_4") (pintype "passive"))
    )
    (net (code "75") (name "Net-(VD2-Anode_{slash}_Cathode)") (class "Default")
      (node (ref "R18") (pin "2") (pinfunction "2_2") (pintype "passive"))
      (node (ref "VD2") (pin "1") (pinfunction "Anode_/_Cathode_1") (pintype "passive"))
    )
    (net (code "76") (name "Net-(VD2-Collector)") (class "Default")
      (node (ref "J2") (pin "1") (pinfunction "1_1") (pintype "passive"))
      (node (ref "VD2") (pin "4") (pinfunction "Collector_4") (pintype "passive"))
    )
    (net (code "77") (name "Net-(VD3-Anode_{slash}_Cathode)") (class "Default")
      (node (ref "R19") (pin "2") (pinfunction "2_2") (pintype "passive"))
      (node (ref "VD3") (pin "1") (pinfunction "Anode_/_Cathode_1") (pintype "passive"))
    )
    (net (code "78") (name "Net-(VD3-Collector)") (class "Default")
      (node (ref "J3") (pin "1") (pinfunction "1_1") (pintype "passive"))
      (node (ref "VD3") (pin "4") (pinfunction "Collector_4") (pintype "passive"))
    )
    (net (code "79") (name "Net-(VD4-Anode_{slash}_Cathode)") (class "Default")
      (node (ref "R20") (pin "2") (pinfunction "2_2") (pintype "passive"))
      (node (ref "VD4") (pin "1") (pinfunction "Anode_/_Cathode_1") (pintype "passive"))
    )
    (net (code "80") (name "Net-(VD4-Collector)") (class "Default")
      (node (ref "J4") (pin "1") (pinfunction "1_1") (pintype "passive"))
      (node (ref "VD4") (pin "4") (pinfunction "Collector_4") (pintype "passive"))
    )
    (net (code "81") (name "Net-(VD5-Anode_{slash}_Cathode)") (class "Default")
      (node (ref "R41") (pin "2") (pinfunction "2_2") (pintype "passive"))
      (node (ref "VD5") (pin "1") (pinfunction "Anode_/_Cathode_1") (pintype "passive"))
    )
    (net (code "82") (name "Net-(VD5-Collector)") (class "Default")
      (node (ref "J5") (pin "1") (pinfunction "1_1") (pintype "passive"))
      (node (ref "VD5") (pin "4") (pinfunction "Collector_4") (pintype "passive"))
    )
    (net (code "83") (name "Net-(VD6-Anode_{slash}_Cathode)") (class "Default")
      (node (ref "R42") (pin "2") (pinfunction "2_2") (pintype "passive"))
      (node (ref "VD6") (pin "1") (pinfunction "Anode_/_Cathode_1") (pintype "passive"))
    )
    (net (code "84") (name "Net-(VD6-Collector)") (class "Default")
      (node (ref "J6") (pin "1") (pinfunction "1_1") (pintype "passive"))
      (node (ref "VD6") (pin "4") (pinfunction "Collector_4") (pintype "passive"))
    )
    (net (code "85") (name "Net-(VD7-Anode_{slash}_Cathode)") (class "Default")
      (node (ref "R43") (pin "2") (pinfunction "2_2") (pintype "passive"))
      (node (ref "VD7") (pin "1") (pinfunction "Anode_/_Cathode_1") (pintype "passive"))
    )
    (net (code "86") (name "Net-(VD7-Collector)") (class "Default")
      (node (ref "J7") (pin "1") (pinfunction "1_1") (pintype "passive"))
      (node (ref "VD7") (pin "4") (pinfunction "Collector_4") (pintype "passive"))
    )
    (net (code "87") (name "Net-(VD8-Anode_{slash}_Cathode)") (class "Default")
      (node (ref "R44") (pin "2") (pinfunction "2_2") (pintype "passive"))
      (node (ref "VD8") (pin "1") (pinfunction "Anode_/_Cathode_1") (pintype "passive"))
    )
    (net (code "88") (name "Net-(VD8-Collector)") (class "Default")
      (node (ref "J8") (pin "1") (pinfunction "1_1") (pintype "passive"))
      (node (ref "VD8") (pin "4") (pinfunction "Collector_4") (pintype "passive"))
    )
  )
)
